# Grove_PIR_Sensor_v1_2.net
KiCad netlist of a schematic drawn in EAGLE
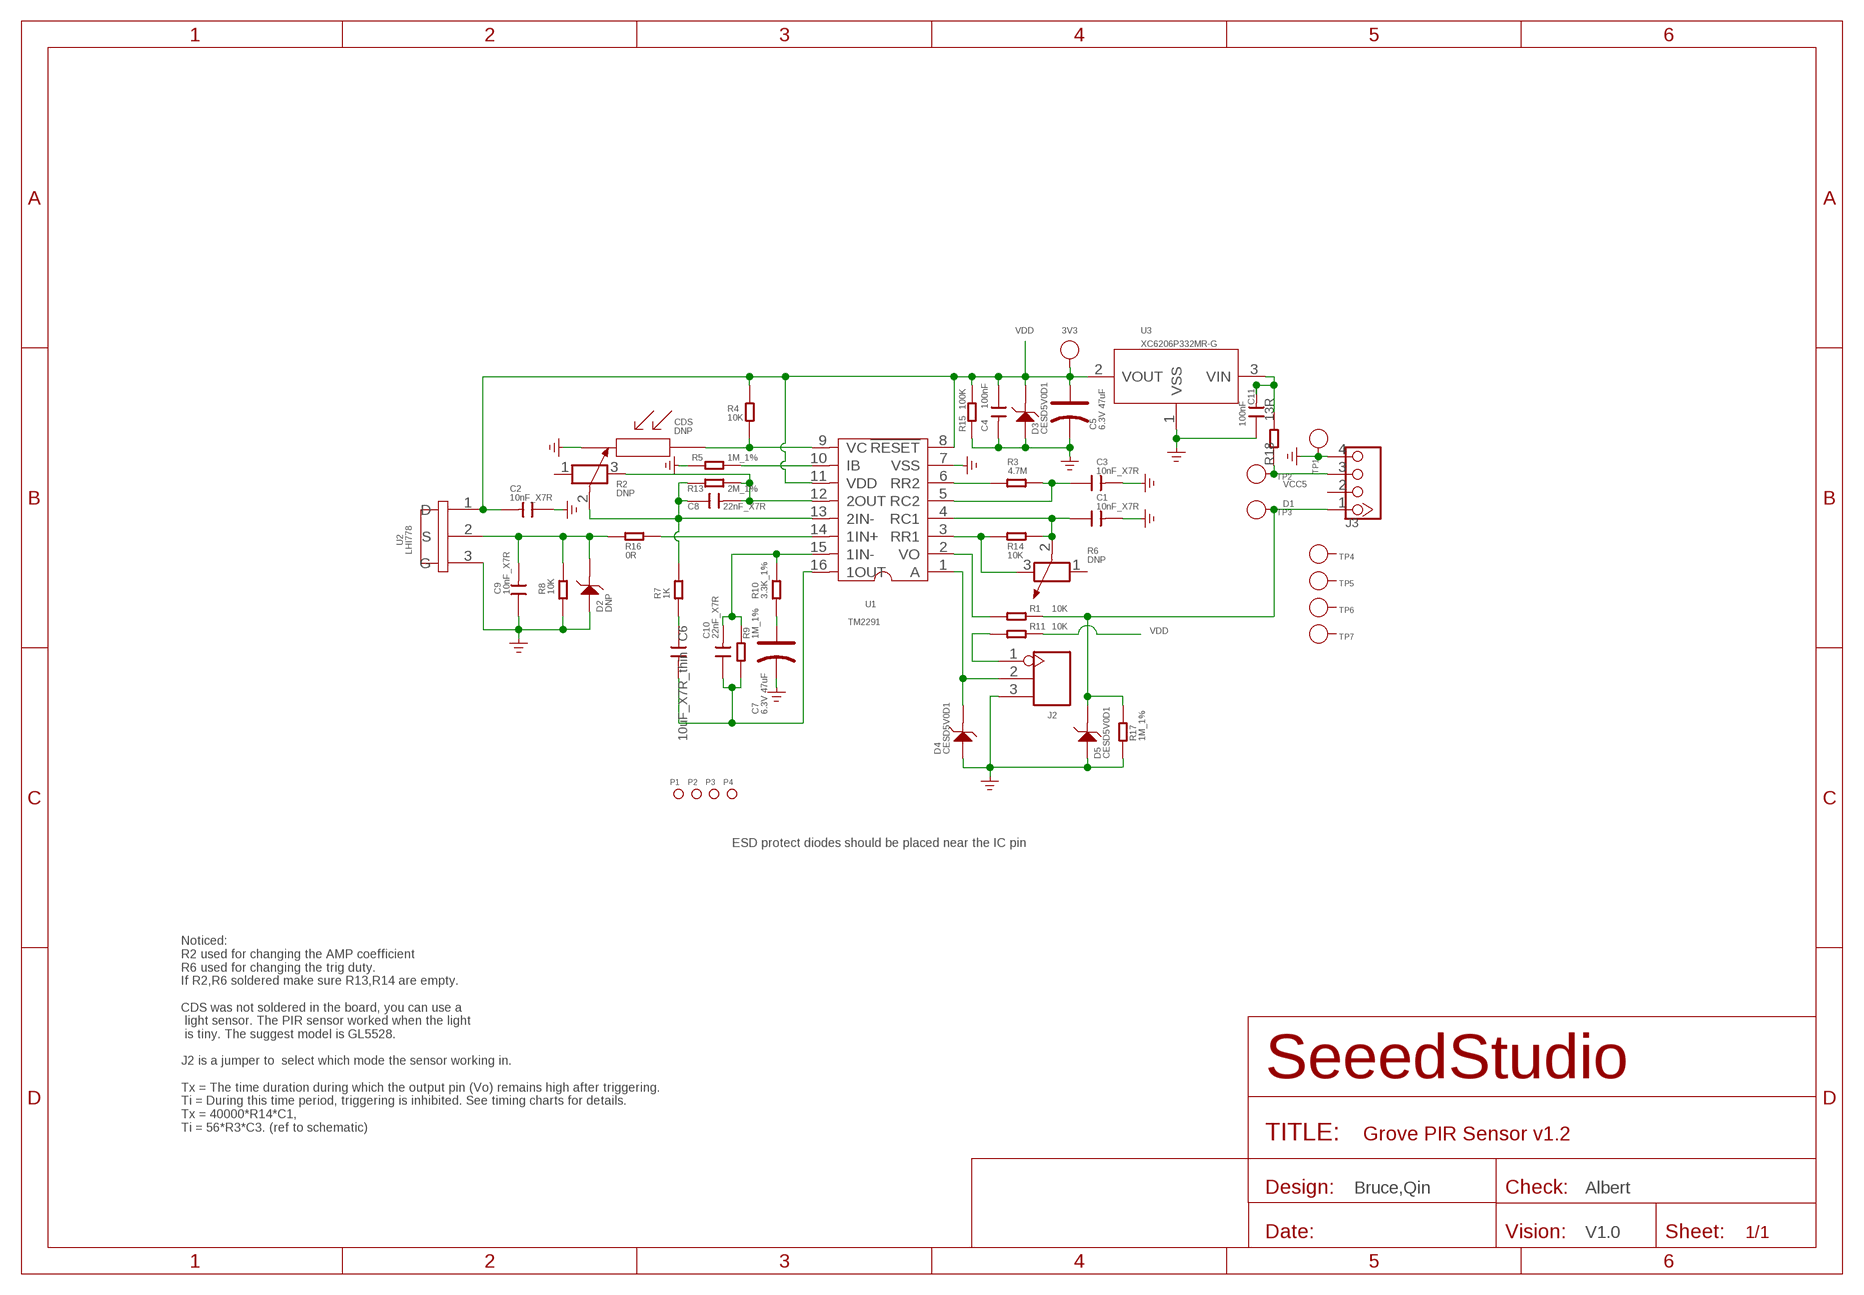
[diagram p0: schematic, sheet 1]

(export (version "E")
  (design (tool "Eeschema 10.0.6"))
  (components
    (comp (ref "3V3")
      (value "PAD-TEST-POINT'3535'")
      (footprint "eagle-import:TP_3535")
      (fields (field (name "PARTNO") "DNP"))
      (libsource (lib "eagle-import") (part "PAD-TEST-POINT'3535'"))
    )
    (comp (ref "C1")
      (value "10nF_X7R")
      (footprint "eagle-import:C0603")
      (libsource (lib "eagle-import") (part "C-0603"))
    )
    (comp (ref "C2")
      (value "10nF_X7R")
      (footprint "eagle-import:C0603")
      (libsource (lib "eagle-import") (part "C-0603"))
    )
    (comp (ref "C3")
      (value "10nF_X7R")
      (footprint "eagle-import:C0603")
      (libsource (lib "eagle-import") (part "C-0603"))
    )
    (comp (ref "C4")
      (value "100nF")
      (footprint "eagle-import:C0603")
      (libsource (lib "eagle-import") (part "C-0603"))
    )
    (comp (ref "C5")
      (value "6.3V 47uF")
      (footprint "eagle-import:AVX-A")
      (libsource (lib "eagle-import") (part "CAP-AVX-A"))
    )
    (comp (ref "C6")
      (value "10uF_X7R_thin")
      (footprint "eagle-import:C0805")
      (libsource (lib "eagle-import") (part "C-0805"))
    )
    (comp (ref "C7")
      (value "6.3V 47uF")
      (footprint "eagle-import:AVX-A")
      (libsource (lib "eagle-import") (part "CAP-AVX-A"))
    )
    (comp (ref "C8")
      (value "22nF_X7R")
      (footprint "eagle-import:C0603")
      (libsource (lib "eagle-import") (part "C-0603"))
    )
    (comp (ref "C9")
      (value "10nF_X7R")
      (footprint "eagle-import:C0603")
      (libsource (lib "eagle-import") (part "C-0603"))
    )
    (comp (ref "C10")
      (value "22nF_X7R")
      (footprint "eagle-import:C0603")
      (libsource (lib "eagle-import") (part "C-0603"))
    )
    (comp (ref "C11")
      (value "100nF")
      (footprint "eagle-import:C0603")
      (libsource (lib "eagle-import") (part "C-0603"))
    )
    (comp (ref "CDS")
      (value "DNP")
      (footprint "eagle-import:CDS")
      (libsource (lib "eagle-import") (part "CDS"))
    )
    (comp (ref "D2")
      (value "DNP")
      (footprint "eagle-import:SOD123-2.7X1.6")
      (libsource (lib "eagle-import") (part "D-ESD-2P'CESD5V0D1'"))
    )
    (comp (ref "D3")
      (value "CESD5V0D1")
      (footprint "eagle-import:SOD123-2.7X1.6")
      (libsource (lib "eagle-import") (part "D-ESD-2P'CESD5V0D1'"))
    )
    (comp (ref "D4")
      (value "CESD5V0D1")
      (footprint "eagle-import:SOD123-2.7X1.6")
      (libsource (lib "eagle-import") (part "D-ESD-2P'CESD5V0D1'"))
    )
    (comp (ref "D5")
      (value "CESD5V0D1")
      (footprint "eagle-import:SOD123-2.7X1.6")
      (libsource (lib "eagle-import") (part "D-ESD-2P'CESD5V0D1'"))
    )
    (comp (ref "J2")
      (value "HEADER-3P-2.54")
      (footprint "eagle-import:3P-2.54")
      (libsource (lib "eagle-import") (part "HEADER-3P-2.54"))
    )
    (comp (ref "J3")
      (value "TWIG-4P-2.0-2.0")
      (footprint "eagle-import:4P-2.0")
      (libsource (lib "eagle-import") (part "TWIG-4P-2.0-2.0"))
    )
    (comp (ref "P1")
      (value "PAD-MARK")
      (footprint "eagle-import:ROUND-MARK-1.0")
      (fields (field (name "PARTNO") "DNP"))
      (libsource (lib "eagle-import") (part "PAD-MARK"))
    )
    (comp (ref "P2")
      (value "PAD-MARK")
      (footprint "eagle-import:ROUND-MARK-1.0")
      (fields (field (name "PARTNO") "DNP"))
      (libsource (lib "eagle-import") (part "PAD-MARK"))
    )
    (comp (ref "P3")
      (value "PAD-MARK")
      (footprint "eagle-import:ROUND-MARK-1.0")
      (fields (field (name "PARTNO") "DNP"))
      (libsource (lib "eagle-import") (part "PAD-MARK"))
    )
    (comp (ref "P4")
      (value "PAD-MARK")
      (footprint "eagle-import:ROUND-MARK-1.0")
      (fields (field (name "PARTNO") "DNP"))
      (libsource (lib "eagle-import") (part "PAD-MARK"))
    )
    (comp (ref "R1")
      (value "10K")
      (footprint "eagle-import:R0603")
      (libsource (lib "eagle-import") (part "R-0603"))
    )
    (comp (ref "R2")
      (value "DNP")
      (footprint "eagle-import:3P-SMD-SQUA-3.6X3.3")
      (libsource (lib "eagle-import") (part "R-POTENTIOMETER-SMD"))
    )
    (comp (ref "R3")
      (value "4.7M")
      (footprint "eagle-import:R0603")
      (libsource (lib "eagle-import") (part "R-0603"))
    )
    (comp (ref "R4")
      (value "10K")
      (footprint "eagle-import:R0603")
      (libsource (lib "eagle-import") (part "R-0603"))
    )
    (comp (ref "R5")
      (value "1M_1%")
      (footprint "eagle-import:R0603")
      (libsource (lib "eagle-import") (part "R-0603"))
    )
    (comp (ref "R6")
      (value "DNP")
      (footprint "eagle-import:3P-SMD-SQUA-3.6X3.3")
      (libsource (lib "eagle-import") (part "R-POTENTIOMETER-SMD"))
    )
    (comp (ref "R7")
      (value "1K")
      (footprint "eagle-import:R0603")
      (libsource (lib "eagle-import") (part "R-0603"))
    )
    (comp (ref "R8")
      (value "10K")
      (footprint "eagle-import:R0603")
      (libsource (lib "eagle-import") (part "R-0603"))
    )
    (comp (ref "R9")
      (value "1M_1%")
      (footprint "eagle-import:R0603")
      (libsource (lib "eagle-import") (part "R-0603"))
    )
    (comp (ref "R10")
      (value "3.3K_1%")
      (footprint "eagle-import:R0603")
      (libsource (lib "eagle-import") (part "R-0603"))
    )
    (comp (ref "R11")
      (value "10K")
      (footprint "eagle-import:R0603")
      (libsource (lib "eagle-import") (part "R-0603"))
    )
    (comp (ref "R13")
      (value "2M_1%")
      (footprint "eagle-import:R0603")
      (libsource (lib "eagle-import") (part "R-0603"))
    )
    (comp (ref "R14")
      (value "10K")
      (footprint "eagle-import:R0603")
      (libsource (lib "eagle-import") (part "R-0603"))
    )
    (comp (ref "R15")
      (value "100K")
      (footprint "eagle-import:R0603")
      (libsource (lib "eagle-import") (part "R-0603"))
    )
    (comp (ref "R16")
      (value "0R")
      (footprint "eagle-import:R0603")
      (libsource (lib "eagle-import") (part "R-0603"))
    )
    (comp (ref "R17")
      (value "1M_1%")
      (footprint "eagle-import:R0603")
      (libsource (lib "eagle-import") (part "R-0603"))
    )
    (comp (ref "R18")
      (value "13R")
      (footprint "eagle-import:R1206")
      (libsource (lib "eagle-import") (part "R-1206"))
    )
    (comp (ref "TP1")
      (value "PAD-TEST-POINT'3535'")
      (footprint "eagle-import:TP_3535")
      (fields (field (name "PARTNO") "DNP"))
      (libsource (lib "eagle-import") (part "PAD-TEST-POINT'3535'"))
    )
    (comp (ref "TP2")
      (value "PAD-TEST-POINT'3535'")
      (footprint "eagle-import:TP_3535")
      (fields (field (name "PARTNO") "DNP"))
      (libsource (lib "eagle-import") (part "PAD-TEST-POINT'3535'"))
    )
    (comp (ref "TP3")
      (value "PAD-TEST-POINT'3535'")
      (footprint "eagle-import:TP_3535")
      (fields (field (name "PARTNO") "DNP"))
      (libsource (lib "eagle-import") (part "PAD-TEST-POINT'3535'"))
    )
    (comp (ref "TP4")
      (value "PAD-TEST-POINT'3535'")
      (footprint "eagle-import:TP_3535")
      (fields (field (name "PARTNO") "DNP"))
      (libsource (lib "eagle-import") (part "PAD-TEST-POINT'3535'"))
    )
    (comp (ref "TP5")
      (value "PAD-TEST-POINT'3535'")
      (footprint "eagle-import:TP_3535")
      (fields (field (name "PARTNO") "DNP"))
      (libsource (lib "eagle-import") (part "PAD-TEST-POINT'3535'"))
    )
    (comp (ref "TP6")
      (value "PAD-TEST-POINT'3535'")
      (footprint "eagle-import:TP_3535")
      (fields (field (name "PARTNO") "DNP"))
      (libsource (lib "eagle-import") (part "PAD-TEST-POINT'3535'"))
    )
    (comp (ref "TP7")
      (value "PAD-TEST-POINT'3535'")
      (footprint "eagle-import:TP_3535")
      (fields (field (name "PARTNO") "DNP"))
      (libsource (lib "eagle-import") (part "PAD-TEST-POINT'3535'"))
    )
    (comp (ref "U1")
      (value "TM2291")
      (footprint "eagle-import:SOP16")
      (libsource (lib "eagle-import") (part "TM2291"))
    )
    (comp (ref "U2")
      (value "LHI778")
      (footprint "eagle-import:3P-D8.1MM")
      (libsource (lib "eagle-import") (part "LHI778"))
    )
    (comp (ref "U3")
      (value "XC6206P332MR-G")
      (footprint "eagle-import:SOT23")
      (libsource (lib "eagle-import") (part "XC6206MR"))
    )
  )
  (nets
    (net (code "1") (name "/D1") (class "Default")
      (node (ref "D5") (pin "2") (pinfunction "2_2") (pintype "bidirectional"))
      (node (ref "J3") (pin "1") (pinfunction "1_1") (pintype "bidirectional"))
      (node (ref "R1") (pin "1") (pinfunction "1_1") (pintype "passive"))
      (node (ref "R17") (pin "2") (pinfunction "2_2") (pintype "passive"))
      (node (ref "TP3") (pin "T") (pinfunction "T_T") (pintype "bidirectional"))
    )
    (net (code "2") (name "/VCC5") (class "Default")
      (node (ref "J3") (pin "3") (pinfunction "3_3") (pintype "bidirectional"))
      (node (ref "R18") (pin "1") (pinfunction "1_1") (pintype "passive"))
      (node (ref "TP2") (pin "T") (pinfunction "T_T") (pintype "bidirectional"))
    )
    (net (code "3") (name "/VDD") (class "Default")
      (node (ref "3V3") (pin "T") (pinfunction "T_T") (pintype "bidirectional"))
      (node (ref "C2") (pin "2") (pinfunction "2_2") (pintype "passive"))
      (node (ref "C4") (pin "1") (pinfunction "1_1") (pintype "passive"))
      (node (ref "C5") (pin "+") (pinfunction "+_+") (pintype "passive"))
      (node (ref "D3") (pin "2") (pinfunction "2_2") (pintype "bidirectional"))
      (node (ref "R11") (pin "1") (pinfunction "1_1") (pintype "passive"))
      (node (ref "R15") (pin "1") (pinfunction "1_1") (pintype "passive"))
      (node (ref "R4") (pin "1") (pinfunction "1_1") (pintype "passive"))
      (node (ref "U1") (pin "11") (pinfunction "VDD_11") (pintype "power_in"))
      (node (ref "U1") (pin "8") (pinfunction "~{RESET}_8") (pintype "input"))
      (node (ref "U2") (pin "1") (pinfunction "D_1") (pintype "bidirectional"))
      (node (ref "U3") (pin "2") (pinfunction "VOUT_2") (pintype "output"))
    )
    (net (code "4") (name "GND_POWER") (class "Default")
      (node (ref "C1") (pin "2") (pinfunction "2_2") (pintype "passive"))
      (node (ref "C11") (pin "1") (pinfunction "1_1") (pintype "passive"))
      (node (ref "C2") (pin "1") (pinfunction "1_1") (pintype "passive"))
      (node (ref "C3") (pin "2") (pinfunction "2_2") (pintype "passive"))
      (node (ref "C4") (pin "2") (pinfunction "2_2") (pintype "passive"))
      (node (ref "C5") (pin "-") (pinfunction "-_-") (pintype "passive"))
      (node (ref "C7") (pin "-") (pinfunction "-_-") (pintype "passive"))
      (node (ref "C9") (pin "1") (pinfunction "1_1") (pintype "passive"))
      (node (ref "CDS") (pin "1") (pinfunction "P$1_1") (pintype "bidirectional"))
      (node (ref "D2") (pin "1") (pinfunction "1_1") (pintype "bidirectional"))
      (node (ref "D3") (pin "1") (pinfunction "1_1") (pintype "bidirectional"))
      (node (ref "D4") (pin "1") (pinfunction "1_1") (pintype "bidirectional"))
      (node (ref "D5") (pin "1") (pinfunction "1_1") (pintype "bidirectional"))
      (node (ref "J2") (pin "3") (pinfunction "P$3_3") (pintype "bidirectional"))
      (node (ref "J3") (pin "4") (pinfunction "4_4") (pintype "bidirectional"))
      (node (ref "R15") (pin "2") (pinfunction "2_2") (pintype "passive"))
      (node (ref "R17") (pin "1") (pinfunction "1_1") (pintype "passive"))
      (node (ref "R5") (pin "1") (pinfunction "1_1") (pintype "passive"))
      (node (ref "R8") (pin "1") (pinfunction "1_1") (pintype "passive"))
      (node (ref "TP1") (pin "T") (pinfunction "T_T") (pintype "bidirectional"))
      (node (ref "U1") (pin "7") (pinfunction "VSS_7") (pintype "power_in"))
      (node (ref "U2") (pin "3") (pinfunction "G_3") (pintype "bidirectional"))
      (node (ref "U3") (pin "1") (pinfunction "VSS_1") (pintype "power_in"))
    )
    (net (code "5") (name "Net-(C6-Pad1)") (class "Default")
      (node (ref "C6") (pin "1") (pinfunction "1_1") (pintype "passive"))
      (node (ref "R7") (pin "1") (pinfunction "1_1") (pintype "passive"))
    )
    (net (code "6") (name "Net-(C7-Pad+)") (class "Default")
      (node (ref "C7") (pin "+") (pinfunction "+_+") (pintype "passive"))
      (node (ref "R10") (pin "1") (pinfunction "1_1") (pintype "passive"))
    )
    (net (code "7") (name "Net-(CDS-P$2)") (class "Default")
      (node (ref "CDS") (pin "2") (pinfunction "P$2_2") (pintype "bidirectional"))
      (node (ref "R4") (pin "2") (pinfunction "2_2") (pintype "passive"))
      (node (ref "U1") (pin "9") (pinfunction "VC_9") (pintype "bidirectional"))
    )
    (net (code "8") (name "Net-(J2-P$1)") (class "Default")
      (node (ref "J2") (pin "1") (pinfunction "P$1_1") (pintype "bidirectional"))
      (node (ref "R11") (pin "2") (pinfunction "2_2") (pintype "passive"))
    )
    (net (code "9") (name "Net-(J2-P$2)") (class "Default")
      (node (ref "D4") (pin "2") (pinfunction "2_2") (pintype "bidirectional"))
      (node (ref "J2") (pin "2") (pinfunction "P$2_2") (pintype "bidirectional"))
      (node (ref "U1") (pin "1") (pinfunction "A_1") (pintype "bidirectional"))
    )
    (net (code "10") (name "Net-(R2-2)") (class "Default")
      (node (ref "C8") (pin "2") (pinfunction "2_2") (pintype "passive"))
      (node (ref "R13") (pin "1") (pinfunction "1_1") (pintype "passive"))
      (node (ref "R2") (pin "3") (pinfunction "2_3") (pintype "passive"))
      (node (ref "U1") (pin "12") (pinfunction "2OUT_12") (pintype "output"))
    )
    (net (code "11") (name "Net-(R2-3)") (class "Default")
      (node (ref "C8") (pin "1") (pinfunction "1_1") (pintype "passive"))
      (node (ref "R13") (pin "2") (pinfunction "2_2") (pintype "passive"))
      (node (ref "R2") (pin "2") (pinfunction "3_2") (pintype "passive"))
      (node (ref "R7") (pin "2") (pinfunction "2_2") (pintype "passive"))
      (node (ref "U1") (pin "13") (pinfunction "2IN-_13") (pintype "input"))
    )
    (net (code "12") (name "Net-(R6-2)") (class "Default")
      (node (ref "R14") (pin "1") (pinfunction "1_1") (pintype "passive"))
      (node (ref "R6") (pin "3") (pinfunction "2_3") (pintype "passive"))
      (node (ref "U1") (pin "3") (pinfunction "RR1_3") (pintype "bidirectional"))
    )
    (net (code "13") (name "Net-(R6-3)") (class "Default")
      (node (ref "C1") (pin "1") (pinfunction "1_1") (pintype "passive"))
      (node (ref "R14") (pin "2") (pinfunction "2_2") (pintype "passive"))
      (node (ref "R6") (pin "2") (pinfunction "3_2") (pintype "passive"))
      (node (ref "U1") (pin "4") (pinfunction "RC1_4") (pintype "bidirectional"))
    )
    (net (code "14") (name "Net-(U1-1IN+)") (class "Default")
      (node (ref "R16") (pin "1") (pinfunction "1_1") (pintype "passive"))
      (node (ref "U1") (pin "14") (pinfunction "1IN+_14") (pintype "input"))
    )
    (net (code "15") (name "Net-(U1-1IN-)") (class "Default")
      (node (ref "C10") (pin "2") (pinfunction "2_2") (pintype "passive"))
      (node (ref "R10") (pin "2") (pinfunction "2_2") (pintype "passive"))
      (node (ref "R9") (pin "2") (pinfunction "2_2") (pintype "passive"))
      (node (ref "U1") (pin "15") (pinfunction "1IN-_15") (pintype "input"))
    )
    (net (code "16") (name "Net-(U1-1OUT)") (class "Default")
      (node (ref "C10") (pin "1") (pinfunction "1_1") (pintype "passive"))
      (node (ref "C6") (pin "2") (pinfunction "2_2") (pintype "passive"))
      (node (ref "R9") (pin "1") (pinfunction "1_1") (pintype "passive"))
      (node (ref "U1") (pin "16") (pinfunction "1OUT_16") (pintype "output"))
    )
    (net (code "17") (name "Net-(U1-IB)") (class "Default")
      (node (ref "R5") (pin "2") (pinfunction "2_2") (pintype "passive"))
      (node (ref "U1") (pin "10") (pinfunction "IB_10") (pintype "bidirectional"))
    )
    (net (code "18") (name "Net-(U1-RC2)") (class "Default")
      (node (ref "C3") (pin "1") (pinfunction "1_1") (pintype "passive"))
      (node (ref "R3") (pin "1") (pinfunction "1_1") (pintype "passive"))
      (node (ref "U1") (pin "5") (pinfunction "RC2_5") (pintype "bidirectional"))
    )
    (net (code "19") (name "Net-(U1-RR2)") (class "Default")
      (node (ref "R3") (pin "2") (pinfunction "2_2") (pintype "passive"))
      (node (ref "U1") (pin "6") (pinfunction "RR2_6") (pintype "bidirectional"))
    )
    (net (code "20") (name "Net-(U1-VO)") (class "Default")
      (node (ref "R1") (pin "2") (pinfunction "2_2") (pintype "passive"))
      (node (ref "U1") (pin "2") (pinfunction "VO_2") (pintype "bidirectional"))
    )
    (net (code "21") (name "Net-(U2-S)") (class "Default")
      (node (ref "C9") (pin "2") (pinfunction "2_2") (pintype "passive"))
      (node (ref "D2") (pin "2") (pinfunction "2_2") (pintype "bidirectional"))
      (node (ref "R16") (pin "2") (pinfunction "2_2") (pintype "passive"))
      (node (ref "R8") (pin "2") (pinfunction "2_2") (pintype "passive"))
      (node (ref "U2") (pin "2") (pinfunction "S_2") (pintype "bidirectional"))
    )
    (net (code "22") (name "Net-(U3-VIN)") (class "Default")
      (node (ref "C11") (pin "2") (pinfunction "2_2") (pintype "passive"))
      (node (ref "R18") (pin "2") (pinfunction "2_2") (pintype "passive"))
      (node (ref "U3") (pin "3") (pinfunction "VIN_3") (pintype "input"))
    )
    (net (code "23") (name "unconnected-(J3-Pad2)") (class "Default")
      (node (ref "J3") (pin "2") (pinfunction "2_2") (pintype "bidirectional"))
    )
    (net (code "24") (name "unconnected-(R2-Pad1)") (class "Default")
      (node (ref "R2") (pin "1") (pinfunction "1_1") (pintype "passive"))
    )
    (net (code "25") (name "unconnected-(R6-Pad1)") (class "Default")
      (node (ref "R6") (pin "1") (pinfunction "1_1") (pintype "passive"))
    )
    (net (code "26") (name "unconnected-(TP4-PadT)") (class "Default")
      (node (ref "TP4") (pin "T") (pinfunction "T_T") (pintype "bidirectional"))
    )
    (net (code "27") (name "unconnected-(TP5-PadT)") (class "Default")
      (node (ref "TP5") (pin "T") (pinfunction "T_T") (pintype "bidirectional"))
    )
    (net (code "28") (name "unconnected-(TP6-PadT)") (class "Default")
      (node (ref "TP6") (pin "T") (pinfunction "T_T") (pintype "bidirectional"))
    )
    (net (code "29") (name "unconnected-(TP7-PadT)") (class "Default")
      (node (ref "TP7") (pin "T") (pinfunction "T_T") (pintype "bidirectional"))
    )
  )
)
